# ESP8266_Programmer.net
KiCad netlist of a schematic drawn in EAGLE
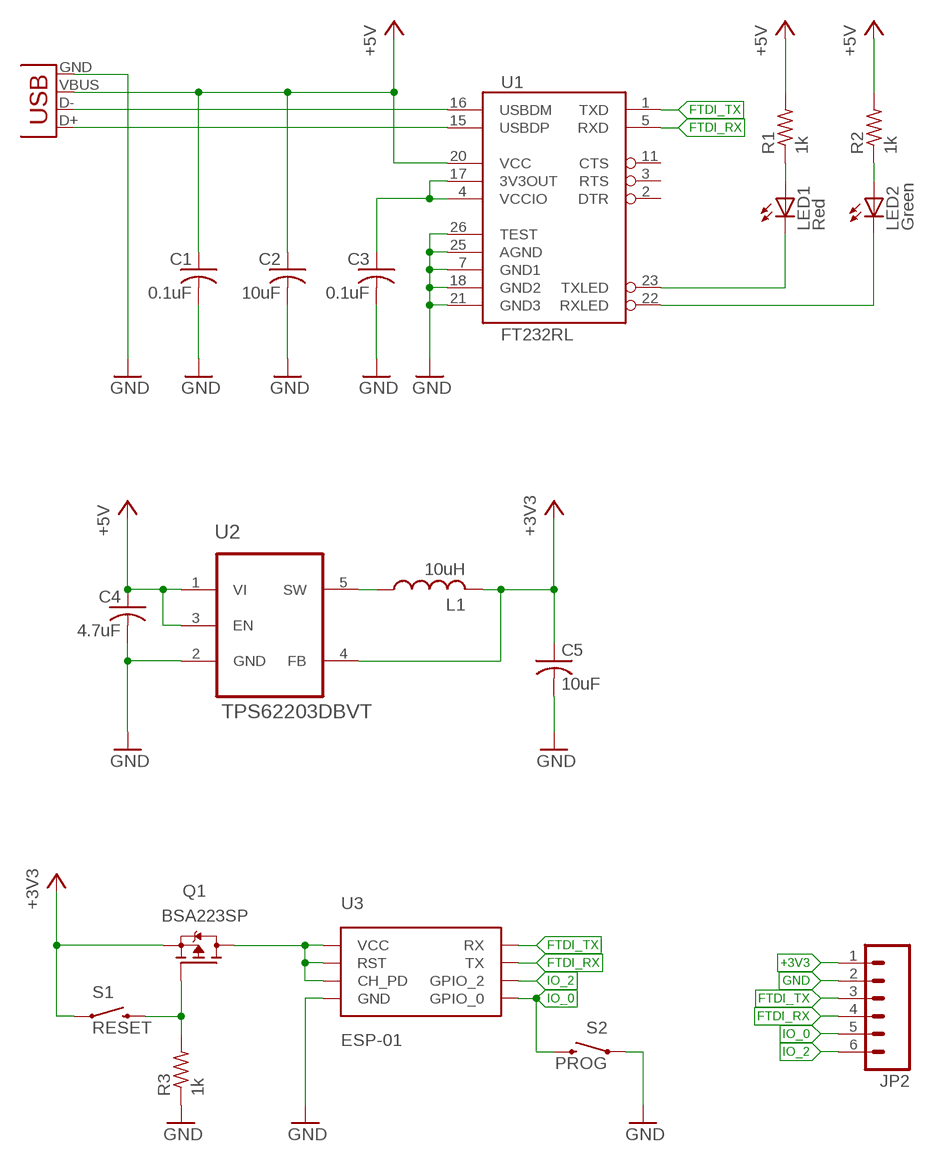
[diagram p0: schematic, sheet 1]

(export (version "E")
  (design (tool "Eeschema 10.0.6"))
  (components
    (comp (ref "C1")
      (value "0.1uF")
      (footprint "eagle-import:C0603")
      (libsource (lib "eagle-import") (part "C-USC0603"))
    )
    (comp (ref "C2")
      (value "10uF")
      (footprint "eagle-import:C0603")
      (libsource (lib "eagle-import") (part "C-USC0603"))
    )
    (comp (ref "C3")
      (value "0.1uF")
      (footprint "eagle-import:C0603")
      (libsource (lib "eagle-import") (part "C-USC0603"))
    )
    (comp (ref "C4")
      (value "4.7uF")
      (footprint "eagle-import:C0603")
      (libsource (lib "eagle-import") (part "C-USC0603"))
    )
    (comp (ref "C5")
      (value "10uF")
      (footprint "eagle-import:C0603")
      (libsource (lib "eagle-import") (part "C-USC0603"))
    )
    (comp (ref "JP1")
      (value "USBSMD")
      (footprint "eagle-import:USB-MINIB")
      (libsource (lib "eagle-import") (part "USBSMD"))
    )
    (comp (ref "JP2")
      (value "M06NO_SILK")
      (footprint "eagle-import:1X06_NO_SILK")
      (libsource (lib "eagle-import") (part "M06NO_SILK"))
    )
    (comp (ref "L1")
      (value "10uH")
      (footprint "eagle-import:L0806")
      (libsource (lib "eagle-import") (part "L-US"))
    )
    (comp (ref "LED1")
      (value "Red")
      (footprint "eagle-import:CHIPLED_0805")
      (libsource (lib "eagle-import") (part "LEDCHIPLED_0805"))
    )
    (comp (ref "LED2")
      (value "Green")
      (footprint "eagle-import:CHIPLED_0805")
      (libsource (lib "eagle-import") (part "LEDCHIPLED_0805"))
    )
    (comp (ref "Q1")
      (value "BSA223SP")
      (footprint "eagle-import:SC75_INFINEON")
      (libsource (lib "eagle-import") (part "BSA223SP"))
    )
    (comp (ref "R1")
      (value "1k")
      (footprint "eagle-import:R0603")
      (libsource (lib "eagle-import") (part "R-US_R0603"))
    )
    (comp (ref "R2")
      (value "1k")
      (footprint "eagle-import:R0603")
      (libsource (lib "eagle-import") (part "R-US_R0603"))
    )
    (comp (ref "R3")
      (value "1k")
      (footprint "eagle-import:R0603")
      (libsource (lib "eagle-import") (part "R-US_R0603"))
    )
    (comp (ref "S1")
      (value "RESET")
      (footprint "eagle-import:TACTILE_SWITCH_TALL")
      (libsource (lib "eagle-import") (part "SWITCH-MOMENTARY-2SMD-4"))
    )
    (comp (ref "S2")
      (value "PROG")
      (footprint "eagle-import:TACTILE_SWITCH_TALL")
      (libsource (lib "eagle-import") (part "SWITCH-MOMENTARY-2SMD-4"))
    )
    (comp (ref "U1")
      (value "FT232RL")
      (footprint "eagle-import:SSOP28DB")
      (libsource (lib "eagle-import") (part "FT232RL-BASICSSOP"))
    )
    (comp (ref "U2")
      (value "TPS62203DBVT")
      (footprint "eagle-import:SOT95P280X145-5N")
      (libsource (lib "eagle-import") (part "TPS62203DBVT"))
    )
    (comp (ref "U3")
      (value "ESP-01")
      (footprint "eagle-import:ESP-01")
      (libsource (lib "eagle-import") (part "ESP-01"))
    )
  )
  (nets
    (net (code "1") (name "+3V3") (class "Default")
      (node (ref "C5") (pin "1") (pinfunction "1_1") (pintype "passive"))
      (node (ref "JP2") (pin "1") (pinfunction "1_1") (pintype "passive"))
      (node (ref "L1") (pin "2") (pinfunction "2_2") (pintype "passive"))
      (node (ref "Q1") (pin "3") (pinfunction "S_3") (pintype "passive"))
      (node (ref "S1") (pin "A2") (pinfunction "1_A2") (pintype "passive"))
      (node (ref "U2") (pin "4") (pinfunction "FB_4") (pintype "input"))
    )
    (net (code "2") (name "+5V") (class "Default")
      (node (ref "C1") (pin "1") (pinfunction "1_1") (pintype "passive"))
      (node (ref "C2") (pin "1") (pinfunction "1_1") (pintype "passive"))
      (node (ref "C4") (pin "1") (pinfunction "1_1") (pintype "passive"))
      (node (ref "JP1") (pin "VBUS") (pinfunction "VBUS_VBUS") (pintype "bidirectional"))
      (node (ref "R1") (pin "2") (pinfunction "2_2") (pintype "passive"))
      (node (ref "R2") (pin "2") (pinfunction "2_2") (pintype "passive"))
      (node (ref "U1") (pin "20") (pinfunction "VCC_20") (pintype "power_in"))
      (node (ref "U2") (pin "1") (pinfunction "VI_1") (pintype "power_in"))
      (node (ref "U2") (pin "3") (pinfunction "EN_3") (pintype "input"))
    )
    (net (code "3") (name "FTDI_RX") (class "Default")
      (node (ref "JP2") (pin "4") (pinfunction "4_4") (pintype "passive"))
      (node (ref "U1") (pin "5") (pinfunction "RXD_5") (pintype "input"))
      (node (ref "U3") (pin "TX") (pinfunction "TX_TX") (pintype "bidirectional"))
    )
    (net (code "4") (name "FTDI_TX") (class "Default")
      (node (ref "JP2") (pin "3") (pinfunction "3_3") (pintype "passive"))
      (node (ref "U1") (pin "1") (pinfunction "TXD_1") (pintype "output"))
      (node (ref "U3") (pin "RX") (pinfunction "RX_RX") (pintype "bidirectional"))
    )
    (net (code "5") (name "GND") (class "Default")
      (node (ref "C1") (pin "2") (pinfunction "2_2") (pintype "passive"))
      (node (ref "C2") (pin "2") (pinfunction "2_2") (pintype "passive"))
      (node (ref "C3") (pin "2") (pinfunction "2_2") (pintype "passive"))
      (node (ref "C4") (pin "2") (pinfunction "2_2") (pintype "passive"))
      (node (ref "C5") (pin "2") (pinfunction "2_2") (pintype "passive"))
      (node (ref "JP1") (pin "GND") (pinfunction "GND_GND") (pintype "bidirectional"))
      (node (ref "JP2") (pin "2") (pinfunction "2_2") (pintype "passive"))
      (node (ref "R3") (pin "1") (pinfunction "1_1") (pintype "passive"))
      (node (ref "S2") (pin "A2") (pinfunction "1_A2") (pintype "passive"))
      (node (ref "U1") (pin "18") (pinfunction "GND2_18") (pintype "power_in"))
      (node (ref "U1") (pin "21") (pinfunction "GND3_21") (pintype "power_in"))
      (node (ref "U1") (pin "25") (pinfunction "AGND_25") (pintype "power_in"))
      (node (ref "U1") (pin "26") (pinfunction "TEST_26") (pintype "input"))
      (node (ref "U1") (pin "7") (pinfunction "GND1_7") (pintype "power_in"))
      (node (ref "U2") (pin "2") (pinfunction "GND_2") (pintype "passive"))
      (node (ref "U3") (pin "GND") (pinfunction "GND_GND") (pintype "bidirectional"))
    )
    (net (code "6") (name "IO_0") (class "Default")
      (node (ref "JP2") (pin "5") (pinfunction "5_5") (pintype "passive"))
      (node (ref "S2") (pin "B2") (pinfunction "2_B2") (pintype "passive"))
      (node (ref "U3") (pin "GPIO_0") (pinfunction "GPIO_0_GPIO_0") (pintype "bidirectional"))
    )
    (net (code "7") (name "IO_2") (class "Default")
      (node (ref "JP2") (pin "6") (pinfunction "6_6") (pintype "passive"))
      (node (ref "U3") (pin "GPIO_2") (pinfunction "GPIO_2_GPIO_2") (pintype "bidirectional"))
    )
    (net (code "8") (name "Net-(LED1-PadA)") (class "Default")
      (node (ref "LED1") (pin "A") (pinfunction "A_A") (pintype "passive"))
      (node (ref "R1") (pin "1") (pinfunction "1_1") (pintype "passive"))
    )
    (net (code "9") (name "Net-(LED2-PadA)") (class "Default")
      (node (ref "LED2") (pin "A") (pinfunction "A_A") (pintype "passive"))
      (node (ref "R2") (pin "1") (pinfunction "1_1") (pintype "passive"))
    )
    (net (code "10") (name "Net-(Q1-D)") (class "Default")
      (node (ref "Q1") (pin "2") (pinfunction "D_2") (pintype "passive"))
      (node (ref "U3") (pin "CH_PD") (pinfunction "CH_PD_CH_PD") (pintype "bidirectional"))
      (node (ref "U3") (pin "RST") (pinfunction "RST_RST") (pintype "bidirectional"))
      (node (ref "U3") (pin "VCC") (pinfunction "VCC_VCC") (pintype "bidirectional"))
    )
    (net (code "11") (name "Net-(Q1-G)") (class "Default")
      (node (ref "Q1") (pin "1") (pinfunction "G_1") (pintype "passive"))
      (node (ref "R3") (pin "2") (pinfunction "2_2") (pintype "passive"))
      (node (ref "S1") (pin "B2") (pinfunction "2_B2") (pintype "passive"))
    )
    (net (code "12") (name "Net-(U1-3V3OUT)") (class "Default")
      (node (ref "C3") (pin "1") (pinfunction "1_1") (pintype "passive"))
      (node (ref "U1") (pin "17") (pinfunction "3V3OUT_17") (pintype "output"))
      (node (ref "U1") (pin "4") (pinfunction "VCCIO_4") (pintype "power_in"))
    )
    (net (code "13") (name "Net-(U1-RXLED)") (class "Default")
      (node (ref "LED2") (pin "C") (pinfunction "C_C") (pintype "passive"))
      (node (ref "U1") (pin "22") (pinfunction "RXLED_22") (pintype "bidirectional"))
    )
    (net (code "14") (name "Net-(U1-TXLED)") (class "Default")
      (node (ref "LED1") (pin "C") (pinfunction "C_C") (pintype "passive"))
      (node (ref "U1") (pin "23") (pinfunction "TXLED_23") (pintype "bidirectional"))
    )
    (net (code "15") (name "Net-(U1-USBDM)") (class "Default")
      (node (ref "JP1") (pin "D-") (pinfunction "D-_D-") (pintype "bidirectional"))
      (node (ref "U1") (pin "16") (pinfunction "USBDM_16") (pintype "bidirectional"))
    )
    (net (code "16") (name "Net-(U1-USBDP)") (class "Default")
      (node (ref "JP1") (pin "D+") (pinfunction "D+_D+") (pintype "bidirectional"))
      (node (ref "U1") (pin "15") (pinfunction "USBDP_15") (pintype "bidirectional"))
    )
    (net (code "17") (name "Net-(U2-SW)") (class "Default")
      (node (ref "L1") (pin "1") (pinfunction "1_1") (pintype "passive"))
      (node (ref "U2") (pin "5") (pinfunction "SW_5") (pintype "output"))
    )
    (net (code "18") (name "unconnected-(U1-CTS-Pad11)") (class "Default")
      (node (ref "U1") (pin "11") (pinfunction "CTS_11") (pintype "bidirectional"))
    )
    (net (code "19") (name "unconnected-(U1-DTR-Pad2)") (class "Default")
      (node (ref "U1") (pin "2") (pinfunction "DTR_2") (pintype "bidirectional"))
    )
    (net (code "20") (name "unconnected-(U1-RTS-Pad3)") (class "Default")
      (node (ref "U1") (pin "3") (pinfunction "RTS_3") (pintype "bidirectional"))
    )
  )
)
